# SINTETIZADOR_Y_MEZCLADOR.net
KiCad netlist of a schematic drawn in Altium Designer
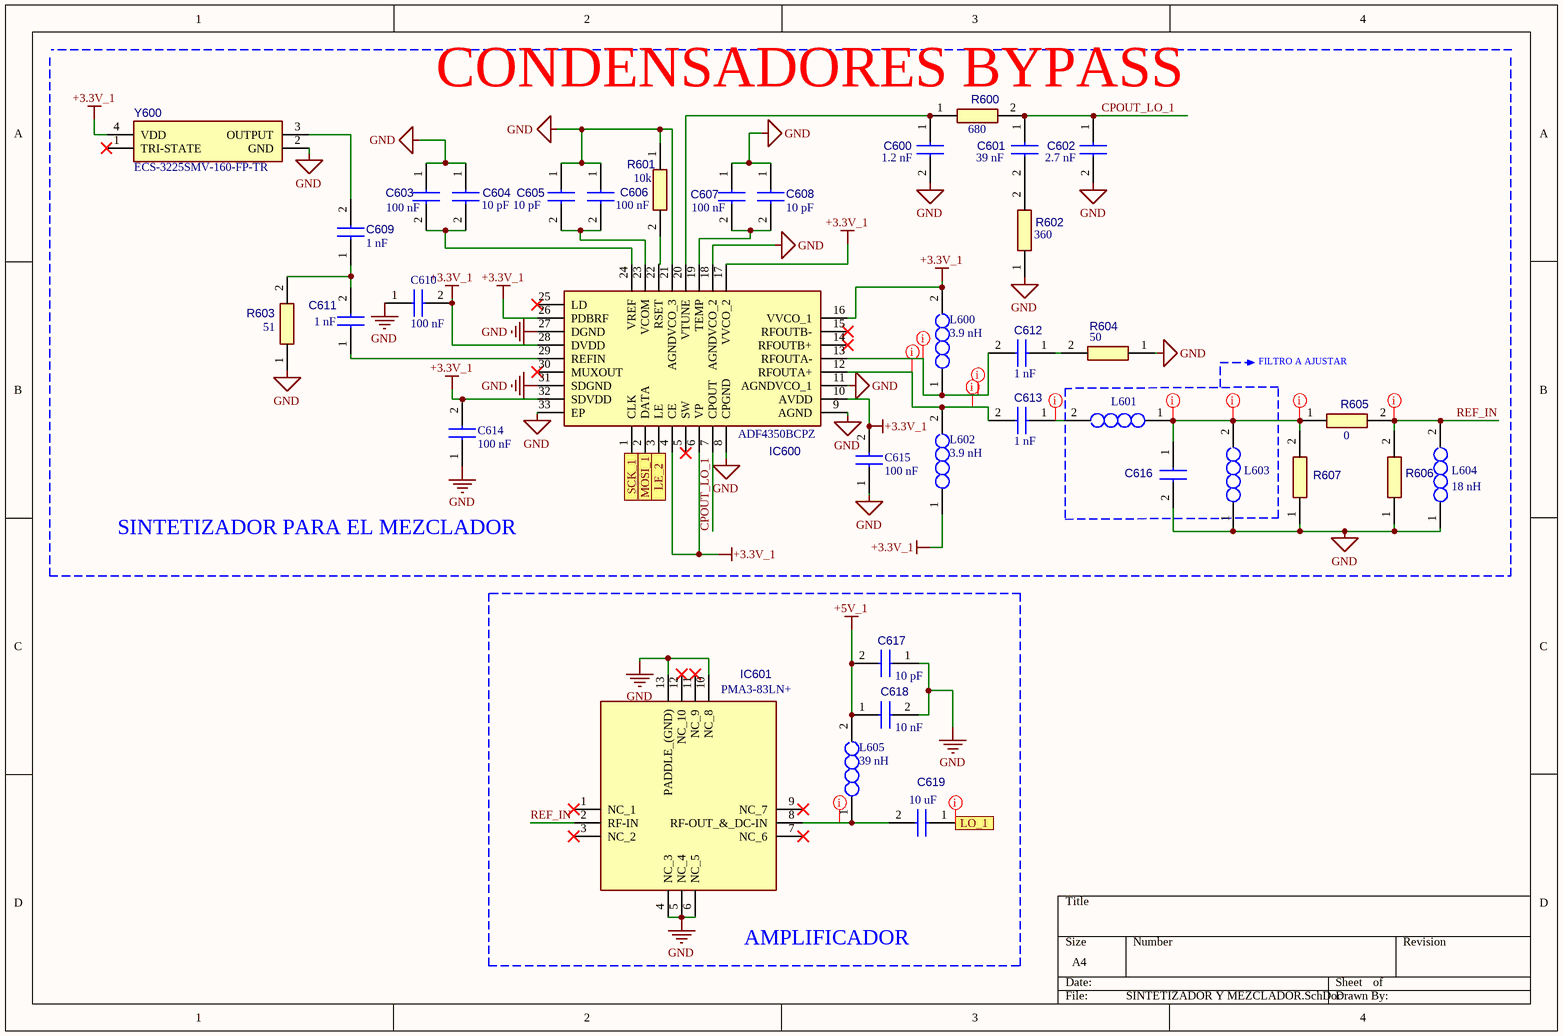
[diagram p0: SINTETIZADOR Y MEZCLADOR.SchDoc]

(export (version "E")
  (design (tool "Eeschema 10.0.6"))
  (components
    (comp (ref "C600")
      (value "1.2 nF")
      (footprint "SamacSys:C0603")
      (description "Capacitor")
      (fields (field (name "MANUFACTURER_PART_NUMBER") "C0603H470J5GACTU"))
      (libsource (lib "*") (part "C0603H470J5GACTU"))
    )
    (comp (ref "C601")
      (value "39 nF")
      (footprint "SamacSys:C0603")
      (description "Capacitor")
      (fields (field (name "MANUFACTURER_PART_NUMBER") "C0603H470J5GACTU"))
      (libsource (lib "*") (part "C0603H470J5GACTU"))
    )
    (comp (ref "C602")
      (value "2.7 nF")
      (footprint "SamacSys:C0603")
      (description "Capacitor")
      (fields (field (name "MANUFACTURER_PART_NUMBER") "C0603H470J5GACTU"))
      (libsource (lib "*") (part "C0603H470J5GACTU"))
    )
    (comp (ref "C603")
      (value "100 nF")
      (footprint "SamacSys:C0603")
      (description "Capacitor")
      (fields (field (name "MANUFACTURER_PART_NUMBER") "C0603H470J5GACTU"))
      (libsource (lib "*") (part "C0603H470J5GACTU"))
    )
    (comp (ref "C604")
      (value "10 pF")
      (footprint "SamacSys:C0603")
      (description "Capacitor")
      (fields (field (name "MANUFACTURER_PART_NUMBER") "C0603H470J5GACTU"))
      (libsource (lib "*") (part "C0603H470J5GACTU"))
    )
    (comp (ref "C605")
      (value "10 pF")
      (footprint "SamacSys:C0603")
      (description "Capacitor")
      (fields (field (name "MANUFACTURER_PART_NUMBER") "C0603H470J5GACTU"))
      (libsource (lib "*") (part "C0603H470J5GACTU"))
    )
    (comp (ref "C606")
      (value "100 nF")
      (footprint "SamacSys:C0603")
      (description "Capacitor")
      (fields (field (name "MANUFACTURER_PART_NUMBER") "C0603H470J5GACTU"))
      (libsource (lib "*") (part "C0603H470J5GACTU"))
    )
    (comp (ref "C607")
      (value "100 nF")
      (footprint "SamacSys:C0603")
      (description "Capacitor")
      (fields (field (name "MANUFACTURER_PART_NUMBER") "C0603H470J5GACTU"))
      (libsource (lib "*") (part "C0603H470J5GACTU"))
    )
    (comp (ref "C608")
      (value "10 pF")
      (footprint "SamacSys:C0603")
      (description "Capacitor")
      (fields (field (name "MANUFACTURER_PART_NUMBER") "C0603H470J5GACTU"))
      (libsource (lib "*") (part "C0603H470J5GACTU"))
    )
    (comp (ref "C609")
      (value "1 nF")
      (footprint "SamacSys:C0603")
      (description "Capacitor")
      (fields (field (name "MANUFACTURER_PART_NUMBER") "C0603H470J5GACTU"))
      (libsource (lib "*") (part "C0603H470J5GACTU"))
    )
    (comp (ref "C610")
      (value "100 nF")
      (footprint "SamacSys:C0603")
      (description "Capacitor")
      (fields (field (name "MANUFACTURER_PART_NUMBER") "C0603H470J5GACTU"))
      (libsource (lib "LIBRERIA_GEN_V2.0") (part "C0603H470J5GACTU"))
    )
    (comp (ref "C611")
      (value "1 nF")
      (footprint "SamacSys:C0603")
      (description "Capacitor")
      (fields (field (name "MANUFACTURER_PART_NUMBER") "C0603H470J5GACTU"))
      (libsource (lib "*") (part "C0603H470J5GACTU"))
    )
    (comp (ref "C612")
      (value "1 nF")
      (footprint "SamacSys:C0603")
      (description "Capacitor")
      (fields (field (name "MANUFACTURER_PART_NUMBER") "C0603H470J5GACTU"))
      (libsource (lib "*") (part "C0603H470J5GACTU"))
    )
    (comp (ref "C613")
      (value "1 nF")
      (footprint "SamacSys:C0603")
      (description "Capacitor")
      (fields (field (name "MANUFACTURER_PART_NUMBER") "C0603H470J5GACTU"))
      (libsource (lib "*") (part "C0603H470J5GACTU"))
    )
    (comp (ref "C614")
      (value "100 nF")
      (footprint "SamacSys:C0603")
      (description "Capacitor")
      (fields (field (name "MANUFACTURER_PART_NUMBER") "C0603H470J5GACTU"))
      (libsource (lib "LIBRERIA_GEN_V2.0") (part "C0603H470J5GACTU"))
    )
    (comp (ref "C615")
      (value "100 nF")
      (footprint "SamacSys:C0603")
      (description "Capacitor")
      (fields (field (name "MANUFACTURER_PART_NUMBER") "C0603H470J5GACTU"))
      (libsource (lib "LIBRERIA_GEN_V2.0") (part "C0603H470J5GACTU"))
    )
    (comp (ref "C616")
      (value "2 pF")
      (footprint "SamacSys:C0603")
      (description "Capacitor")
      (fields (field (name "MANUFACTURER_PART_NUMBER") "C0603H470J5GACTU"))
      (libsource (lib "*") (part "C0603H470J5GACTU"))
    )
    (comp (ref "C617")
      (value "10 pF")
      (footprint "SamacSys:C0603")
      (description "Capacitor")
      (fields (field (name "MANUFACTURER_PART_NUMBER") "C0603H470J5GACTU"))
      (libsource (lib "*") (part "C0603H470J5GACTU"))
    )
    (comp (ref "C618")
      (value "10 nF")
      (footprint "SamacSys:C0603")
      (description "Capacitor")
      (fields (field (name "MANUFACTURER_PART_NUMBER") "C0603H470J5GACTU"))
      (libsource (lib "*") (part "C0603H470J5GACTU"))
    )
    (comp (ref "C619")
      (value "10 uF")
      (footprint "SamacSys:C0603")
      (description "Capacitor")
      (fields (field (name "MANUFACTURER_PART_NUMBER") "C0603H470J5GACTU"))
      (libsource (lib "*") (part "C0603H470J5GACTU"))
    )
    (comp (ref "IC600")
      (value "ADF4350BCPZ")
      (footprint "SamacSys:QFN50P500X500X100-33N")
      (description "Integrated Circuit")
      (fields (field (name "MOUSER PART NUMBER") "584-ADF4350BCPZ"))
      (libsource (lib "*") (part "ADF4350BCPZ"))
    )
    (comp (ref "IC601")
      (value "PMA3-83LN+")
      (footprint "SamacSys:QFN51P300X300X89-13N")
      (description "Integrated Circuit")
      (fields (field (name "MOUSER PART NUMBER") "139-PMA3-83LN"))
      (libsource (lib "*") (part "PMA3-83LN+"))
    )
    (comp (ref "L600")
      (value "3.9 nH")
      (footprint "SamacSys:INDC1608X95N")
      (description "Inductor")
      (fields
        (field (name "MANUFACTURER_PART_NUMBER") "AIML-0603-100K-T")
        (field (name "MOUSER PART NUMBER") "815-AIML-0603-100KT")
      )
      (libsource (lib "*") (part "AIML-0603-100K-T"))
    )
    (comp (ref "L601")
      (value "3.9 nH")
      (footprint "SamacSys:INDC1608X95N")
      (description "Inductor")
      (fields
        (field (name "MANUFACTURER_PART_NUMBER") "AIML-0603-100K-T")
        (field (name "MOUSER PART NUMBER") "815-AIML-0603-100KT")
      )
      (libsource (lib "*") (part "AIML-0603-100K-T"))
    )
    (comp (ref "L602")
      (value "3.9 nH")
      (footprint "SamacSys:INDC1608X95N")
      (description "Inductor")
      (fields
        (field (name "MANUFACTURER_PART_NUMBER") "AIML-0603-100K-T")
        (field (name "MOUSER PART NUMBER") "815-AIML-0603-100KT")
      )
      (libsource (lib "*") (part "AIML-0603-100K-T"))
    )
    (comp (ref "L603")
      (value "1.6 nH")
      (footprint "SamacSys:INDC1608X95N")
      (description "Inductor")
      (fields
        (field (name "MANUFACTURER_PART_NUMBER") "AIML-0603-100K-T")
        (field (name "MOUSER PART NUMBER") "815-AIML-0603-100KT")
      )
      (libsource (lib "*") (part "AIML-0603-100K-T"))
    )
    (comp (ref "L604")
      (value "18 nH")
      (footprint "SamacSys:INDC1608X95N")
      (description "Inductor")
      (fields
        (field (name "MANUFACTURER_PART_NUMBER") "AIML-0603-100K-T")
        (field (name "MOUSER PART NUMBER") "815-AIML-0603-100KT")
      )
      (libsource (lib "*") (part "AIML-0603-100K-T"))
    )
    (comp (ref "L605")
      (value "39 nH")
      (footprint "SamacSys:INDC1608X95N")
      (description "Inductor")
      (fields
        (field (name "MANUFACTURER_PART_NUMBER") "AIML-0603-100K-T")
        (field (name "MOUSER PART NUMBER") "815-AIML-0603-100KT")
      )
      (libsource (lib "*") (part "AIML-0603-100K-T"))
    )
    (comp (ref "R600")
      (value "680")
      (footprint "SamacSys:RESC1608X55N")
      (description "Resistor")
      (fields
        (field (name "MANUFACTURER_PART_NUMBER") "CR0603-FX-1431ELF")
        (field (name "MOUSER PART NUMBER") "652-CR0603FX-1431ELF")
      )
      (libsource (lib "") (part "CR0603-FX-1431ELF_3"))
    )
    (comp (ref "R601")
      (value "10k")
      (footprint "SamacSys:RESC1608X55N")
      (description "Resistor")
      (fields
        (field (name "MANUFACTURER_PART_NUMBER") "CR0603-FX-1431ELF")
        (field (name "MOUSER PART NUMBER") "652-CR0603FX-1431ELF")
      )
      (libsource (lib "*") (part "CR0603-FX-1431ELF"))
    )
    (comp (ref "R602")
      (value "360")
      (footprint "SamacSys:RESC1608X55N")
      (description "Resistor")
      (fields
        (field (name "MANUFACTURER_PART_NUMBER") "CR0603-FX-1431ELF")
        (field (name "MOUSER PART NUMBER") "652-CR0603FX-1431ELF")
      )
      (libsource (lib "") (part "CR0603-FX-1431ELF_1"))
    )
    (comp (ref "R603")
      (value "51")
      (footprint "SamacSys:RESC1608X55N")
      (description "Resistor")
      (fields
        (field (name "MANUFACTURER_PART_NUMBER") "CR0603-FX-1431ELF")
        (field (name "MOUSER PART NUMBER") "652-CR0603FX-1431ELF")
      )
      (libsource (lib "") (part "CR0603-FX-1431ELF_1"))
    )
    (comp (ref "R604")
      (value "50")
      (footprint "SamacSys:RESC1608X55N")
      (description "Resistor")
      (fields
        (field (name "MANUFACTURER_PART_NUMBER") "CR0603-FX-1431ELF")
        (field (name "MOUSER PART NUMBER") "652-CR0603FX-1431ELF")
      )
      (libsource (lib "") (part "CR0603-FX-1431ELF_2"))
    )
    (comp (ref "R605")
      (value "0")
      (footprint "SamacSys:RESC1608X55N")
      (description "Resistor")
      (fields
        (field (name "MANUFACTURER_PART_NUMBER") "CR0603-FX-1431ELF")
        (field (name "MOUSER PART NUMBER") "652-CR0603FX-1431ELF")
      )
      (libsource (lib "") (part "CR0603-FX-1431ELF_3"))
    )
    (comp (ref "R606")
      (value "68")
      (footprint "SamacSys:RESC1608X55N")
      (description "Resistor")
      (fields
        (field (name "MANUFACTURER_PART_NUMBER") "CR0603-FX-1431ELF")
        (field (name "MOUSER PART NUMBER") "652-CR0603FX-1431ELF")
      )
      (libsource (lib "") (part "CR0603-FX-1431ELF_1"))
    )
    (comp (ref "R607")
      (value "68")
      (footprint "SamacSys:RESC1608X55N")
      (description "Resistor")
      (fields
        (field (name "MANUFACTURER_PART_NUMBER") "CR0603-FX-1431ELF")
        (field (name "MOUSER PART NUMBER") "652-CR0603FX-1431ELF")
      )
      (libsource (lib "") (part "CR0603-FX-1431ELF_1"))
    )
    (comp (ref "Y600")
      (value "ECS-3225SMV-160-FP-TR")
      (footprint "SamacSys:ECS3225SMV160FPTR")
      (description "Crystal or Oscillator")
      (fields (field (name "MOUSER PART NUMBER") "520-3225SMV-160-FPT"))
      (libsource (lib "*") (part "ECS-3225SMV-160-FP-TR"))
    )
  )
  (nets
    (net (code "1") (name "+3.3V_1") (class "Default")
      (node (ref "C610") (pin "2") (pinfunction "2_2") (pintype "passive"))
      (node (ref "C614") (pin "2") (pinfunction "2_2") (pintype "passive"))
      (node (ref "C615") (pin "2") (pinfunction "2_2") (pintype "passive"))
      (node (ref "IC600") (pin "10") (pinfunction "AVDD_10") (pintype "passive"))
      (node (ref "IC600") (pin "16") (pinfunction "VVCO_1_16") (pintype "passive"))
      (node (ref "IC600") (pin "17") (pinfunction "VVCO_2_17") (pintype "passive"))
      (node (ref "IC600") (pin "26") (pinfunction "PDBRF_26") (pintype "passive"))
      (node (ref "IC600") (pin "28") (pinfunction "DVDD_28") (pintype "passive"))
      (node (ref "IC600") (pin "32") (pinfunction "SDVDD_32") (pintype "passive"))
      (node (ref "IC600") (pin "4") (pinfunction "CE_4") (pintype "passive"))
      (node (ref "IC600") (pin "6") (pinfunction "VP_6") (pintype "passive"))
      (node (ref "L600") (pin "2") (pinfunction "2_2") (pintype "passive"))
      (node (ref "L602") (pin "1") (pinfunction "1_1") (pintype "passive"))
      (node (ref "Y600") (pin "4") (pinfunction "VDD_4") (pintype "passive"))
    )
    (net (code "2") (name "+5V_1") (class "Default")
      (node (ref "C617") (pin "2") (pinfunction "2_2") (pintype "passive"))
      (node (ref "C618") (pin "1") (pinfunction "1_1") (pintype "passive"))
      (node (ref "L605") (pin "2") (pinfunction "2_2") (pintype "passive"))
    )
    (net (code "3") (name "/CPOUT_LO_1") (class "Default")
      (node (ref "C601") (pin "1") (pinfunction "1_1") (pintype "passive"))
      (node (ref "C602") (pin "1") (pinfunction "1_1") (pintype "passive"))
      (node (ref "IC600") (pin "7") (pinfunction "CPOUT_7") (pintype "passive"))
      (node (ref "R600") (pin "2") (pinfunction "2_2") (pintype "passive"))
    )
    (net (code "4") (name "/LE_2") (class "Default")
      (node (ref "IC600") (pin "3") (pinfunction "LE_3") (pintype "passive"))
    )
    (net (code "5") (name "/LO_1") (class "Default")
      (node (ref "C619") (pin "1") (pinfunction "1_1") (pintype "passive"))
    )
    (net (code "6") (name "/MOSI_1") (class "Default")
      (node (ref "IC600") (pin "2") (pinfunction "DATA_2") (pintype "passive"))
    )
    (net (code "7") (name "/REF_IN") (class "Default")
      (node (ref "IC601") (pin "2") (pinfunction "RF-IN_2") (pintype "passive"))
      (node (ref "L604") (pin "2") (pinfunction "2_2") (pintype "passive"))
      (node (ref "R605") (pin "2") (pinfunction "2_2") (pintype "passive"))
      (node (ref "R606") (pin "2") (pinfunction "2_2") (pintype "passive"))
    )
    (net (code "8") (name "/SCK_1") (class "Default")
      (node (ref "IC600") (pin "1") (pinfunction "CLK_1") (pintype "passive"))
    )
    (net (code "9") (name "GND") (class "Default")
      (node (ref "C600") (pin "2") (pinfunction "2_2") (pintype "passive"))
      (node (ref "C602") (pin "2") (pinfunction "2_2") (pintype "passive"))
      (node (ref "C603") (pin "1") (pinfunction "1_1") (pintype "passive"))
      (node (ref "C604") (pin "1") (pinfunction "1_1") (pintype "passive"))
      (node (ref "C605") (pin "1") (pinfunction "1_1") (pintype "passive"))
      (node (ref "C606") (pin "1") (pinfunction "1_1") (pintype "passive"))
      (node (ref "C607") (pin "1") (pinfunction "1_1") (pintype "passive"))
      (node (ref "C608") (pin "1") (pinfunction "1_1") (pintype "passive"))
      (node (ref "C610") (pin "1") (pinfunction "1_1") (pintype "passive"))
      (node (ref "C614") (pin "1") (pinfunction "1_1") (pintype "passive"))
      (node (ref "C615") (pin "1") (pinfunction "1_1") (pintype "passive"))
      (node (ref "C616") (pin "2") (pinfunction "2_2") (pintype "passive"))
      (node (ref "C617") (pin "1") (pinfunction "1_1") (pintype "passive"))
      (node (ref "C618") (pin "2") (pinfunction "2_2") (pintype "passive"))
      (node (ref "IC600") (pin "11") (pinfunction "AGNDVCO_1_11") (pintype "passive"))
      (node (ref "IC600") (pin "18") (pinfunction "AGNDVCO_2_18") (pintype "passive"))
      (node (ref "IC600") (pin "21") (pinfunction "AGNDVCO_3_21") (pintype "passive"))
      (node (ref "IC600") (pin "27") (pinfunction "DGND_27") (pintype "passive"))
      (node (ref "IC600") (pin "31") (pinfunction "SDGND_31") (pintype "passive"))
      (node (ref "IC600") (pin "33") (pinfunction "EP_33") (pintype "passive"))
      (node (ref "IC600") (pin "8") (pinfunction "CPGND_8") (pintype "passive"))
      (node (ref "IC600") (pin "9") (pinfunction "AGND_9") (pintype "passive"))
      (node (ref "IC601") (pin "10") (pinfunction "NC_8_10") (pintype "passive"))
      (node (ref "IC601") (pin "13") (pinfunction "PADDLE_(GND)_13") (pintype "passive"))
      (node (ref "IC601") (pin "4") (pinfunction "NC_3_4") (pintype "passive"))
      (node (ref "IC601") (pin "5") (pinfunction "NC_4_5") (pintype "passive"))
      (node (ref "IC601") (pin "6") (pinfunction "NC_5_6") (pintype "passive"))
      (node (ref "L603") (pin "1") (pinfunction "1_1") (pintype "passive"))
      (node (ref "L604") (pin "1") (pinfunction "1_1") (pintype "passive"))
      (node (ref "R601") (pin "1") (pinfunction "1_1") (pintype "passive"))
      (node (ref "R602") (pin "1") (pinfunction "1_1") (pintype "passive"))
      (node (ref "R603") (pin "1") (pinfunction "1_1") (pintype "passive"))
      (node (ref "R604") (pin "1") (pinfunction "1_1") (pintype "passive"))
      (node (ref "R606") (pin "1") (pinfunction "1_1") (pintype "passive"))
      (node (ref "R607") (pin "1") (pinfunction "1_1") (pintype "passive"))
      (node (ref "Y600") (pin "2") (pinfunction "GND_2") (pintype "passive"))
    )
    (net (code "10") (name "Net-(C601-Pad2)") (class "Default")
      (node (ref "C601") (pin "2") (pinfunction "2_2") (pintype "passive"))
      (node (ref "R602") (pin "2") (pinfunction "2_2") (pintype "passive"))
    )
    (net (code "11") (name "Net-(C609-Pad1)") (class "Default")
      (node (ref "C609") (pin "1") (pinfunction "1_1") (pintype "passive"))
      (node (ref "C611") (pin "2") (pinfunction "2_2") (pintype "passive"))
      (node (ref "R603") (pin "2") (pinfunction "2_2") (pintype "passive"))
    )
    (net (code "12") (name "Net-(C612-Pad1)") (class "Default")
      (node (ref "C612") (pin "1") (pinfunction "1_1") (pintype "passive"))
      (node (ref "R604") (pin "2") (pinfunction "2_2") (pintype "passive"))
    )
    (net (code "13") (name "Net-(C613-Pad1)") (class "Default")
      (node (ref "C613") (pin "1") (pinfunction "1_1") (pintype "passive"))
      (node (ref "L601") (pin "2") (pinfunction "2_2") (pintype "passive"))
    )
    (net (code "14") (name "Net-(C616-Pad1)") (class "Default")
      (node (ref "C616") (pin "1") (pinfunction "1_1") (pintype "passive"))
      (node (ref "L601") (pin "1") (pinfunction "1_1") (pintype "passive"))
      (node (ref "L603") (pin "2") (pinfunction "2_2") (pintype "passive"))
      (node (ref "R605") (pin "1") (pinfunction "1_1") (pintype "passive"))
      (node (ref "R607") (pin "2") (pinfunction "2_2") (pintype "passive"))
    )
    (net (code "15") (name "Net-(IC600-REFIN)") (class "Default")
      (node (ref "C611") (pin "1") (pinfunction "1_1") (pintype "passive"))
      (node (ref "IC600") (pin "29") (pinfunction "REFIN_29") (pintype "passive"))
    )
    (net (code "16") (name "Net-(IC600-RFOUTA+)") (class "Default")
      (node (ref "C613") (pin "2") (pinfunction "2_2") (pintype "passive"))
      (node (ref "IC600") (pin "12") (pinfunction "RFOUTA+_12") (pintype "passive"))
      (node (ref "L602") (pin "2") (pinfunction "2_2") (pintype "passive"))
    )
    (net (code "17") (name "Net-(IC600-RFOUTA-)") (class "Default")
      (node (ref "C612") (pin "2") (pinfunction "2_2") (pintype "passive"))
      (node (ref "IC600") (pin "13") (pinfunction "RFOUTA-_13") (pintype "passive"))
      (node (ref "L600") (pin "1") (pinfunction "1_1") (pintype "passive"))
    )
    (net (code "18") (name "Net-(IC600-RSET)") (class "Default")
      (node (ref "IC600") (pin "22") (pinfunction "RSET_22") (pintype "passive"))
      (node (ref "R601") (pin "2") (pinfunction "2_2") (pintype "passive"))
    )
    (net (code "19") (name "Net-(IC600-TEMP)") (class "Default")
      (node (ref "C607") (pin "2") (pinfunction "2_2") (pintype "passive"))
      (node (ref "C608") (pin "2") (pinfunction "2_2") (pintype "passive"))
      (node (ref "IC600") (pin "19") (pinfunction "TEMP_19") (pintype "passive"))
    )
    (net (code "20") (name "Net-(IC600-VCOM)") (class "Default")
      (node (ref "C605") (pin "2") (pinfunction "2_2") (pintype "passive"))
      (node (ref "C606") (pin "2") (pinfunction "2_2") (pintype "passive"))
      (node (ref "IC600") (pin "23") (pinfunction "VCOM_23") (pintype "passive"))
    )
    (net (code "21") (name "Net-(IC600-VREF)") (class "Default")
      (node (ref "C603") (pin "2") (pinfunction "2_2") (pintype "passive"))
      (node (ref "C604") (pin "2") (pinfunction "2_2") (pintype "passive"))
      (node (ref "IC600") (pin "24") (pinfunction "VREF_24") (pintype "passive"))
    )
    (net (code "22") (name "Net-(IC600-VTUNE)") (class "Default")
      (node (ref "C600") (pin "1") (pinfunction "1_1") (pintype "passive"))
      (node (ref "IC600") (pin "20") (pinfunction "VTUNE_20") (pintype "passive"))
      (node (ref "R600") (pin "1") (pinfunction "1_1") (pintype "passive"))
    )
    (net (code "23") (name "Net-(IC601-RF-OUT_&_DC-IN)") (class "Default")
      (node (ref "C619") (pin "2") (pinfunction "2_2") (pintype "passive"))
      (node (ref "IC601") (pin "8") (pinfunction "RF-OUT_&_DC-IN_8") (pintype "passive"))
      (node (ref "L605") (pin "1") (pinfunction "1_1") (pintype "passive"))
    )
    (net (code "24") (name "Net-(Y600-OUTPUT)") (class "Default")
      (node (ref "C609") (pin "2") (pinfunction "2_2") (pintype "passive"))
      (node (ref "Y600") (pin "3") (pinfunction "OUTPUT_3") (pintype "passive"))
    )
    (net (code "25") (name "unconnected-(IC600-LD-Pad25)") (class "Default")
      (node (ref "IC600") (pin "25") (pinfunction "LD_25") (pintype "passive+no_connect"))
    )
    (net (code "26") (name "unconnected-(IC600-MUXOUT-Pad30)") (class "Default")
      (node (ref "IC600") (pin "30") (pinfunction "MUXOUT_30") (pintype "passive+no_connect"))
    )
    (net (code "27") (name "unconnected-(IC600-RFOUTB+-Pad14)") (class "Default")
      (node (ref "IC600") (pin "14") (pinfunction "RFOUTB+_14") (pintype "passive+no_connect"))
    )
    (net (code "28") (name "unconnected-(IC600-RFOUTB--Pad15)") (class "Default")
      (node (ref "IC600") (pin "15") (pinfunction "RFOUTB-_15") (pintype "passive+no_connect"))
    )
    (net (code "29") (name "unconnected-(IC600-SW-Pad5)") (class "Default")
      (node (ref "IC600") (pin "5") (pinfunction "SW_5") (pintype "passive+no_connect"))
    )
    (net (code "30") (name "unconnected-(IC601-NC_1-Pad1)") (class "Default")
      (node (ref "IC601") (pin "1") (pinfunction "NC_1_1") (pintype "passive+no_connect"))
    )
    (net (code "31") (name "unconnected-(IC601-NC_2-Pad3)") (class "Default")
      (node (ref "IC601") (pin "3") (pinfunction "NC_2_3") (pintype "passive+no_connect"))
    )
    (net (code "32") (name "unconnected-(IC601-NC_6-Pad7)") (class "Default")
      (node (ref "IC601") (pin "7") (pinfunction "NC_6_7") (pintype "passive+no_connect"))
    )
    (net (code "33") (name "unconnected-(IC601-NC_7-Pad9)") (class "Default")
      (node (ref "IC601") (pin "9") (pinfunction "NC_7_9") (pintype "passive+no_connect"))
    )
    (net (code "34") (name "unconnected-(IC601-NC_9-Pad11)") (class "Default")
      (node (ref "IC601") (pin "11") (pinfunction "NC_9_11") (pintype "passive+no_connect"))
    )
    (net (code "35") (name "unconnected-(IC601-NC_10-Pad12)") (class "Default")
      (node (ref "IC601") (pin "12") (pinfunction "NC_10_12") (pintype "passive+no_connect"))
    )
    (net (code "36") (name "unconnected-(Y600-TRI-STATE-Pad1)") (class "Default")
      (node (ref "Y600") (pin "1") (pinfunction "TRI-STATE_1") (pintype "passive+no_connect"))
    )
  )
)
